# MJ808_clone_-_all_driver.net
KiCad netlist of a schematic drawn in EAGLE
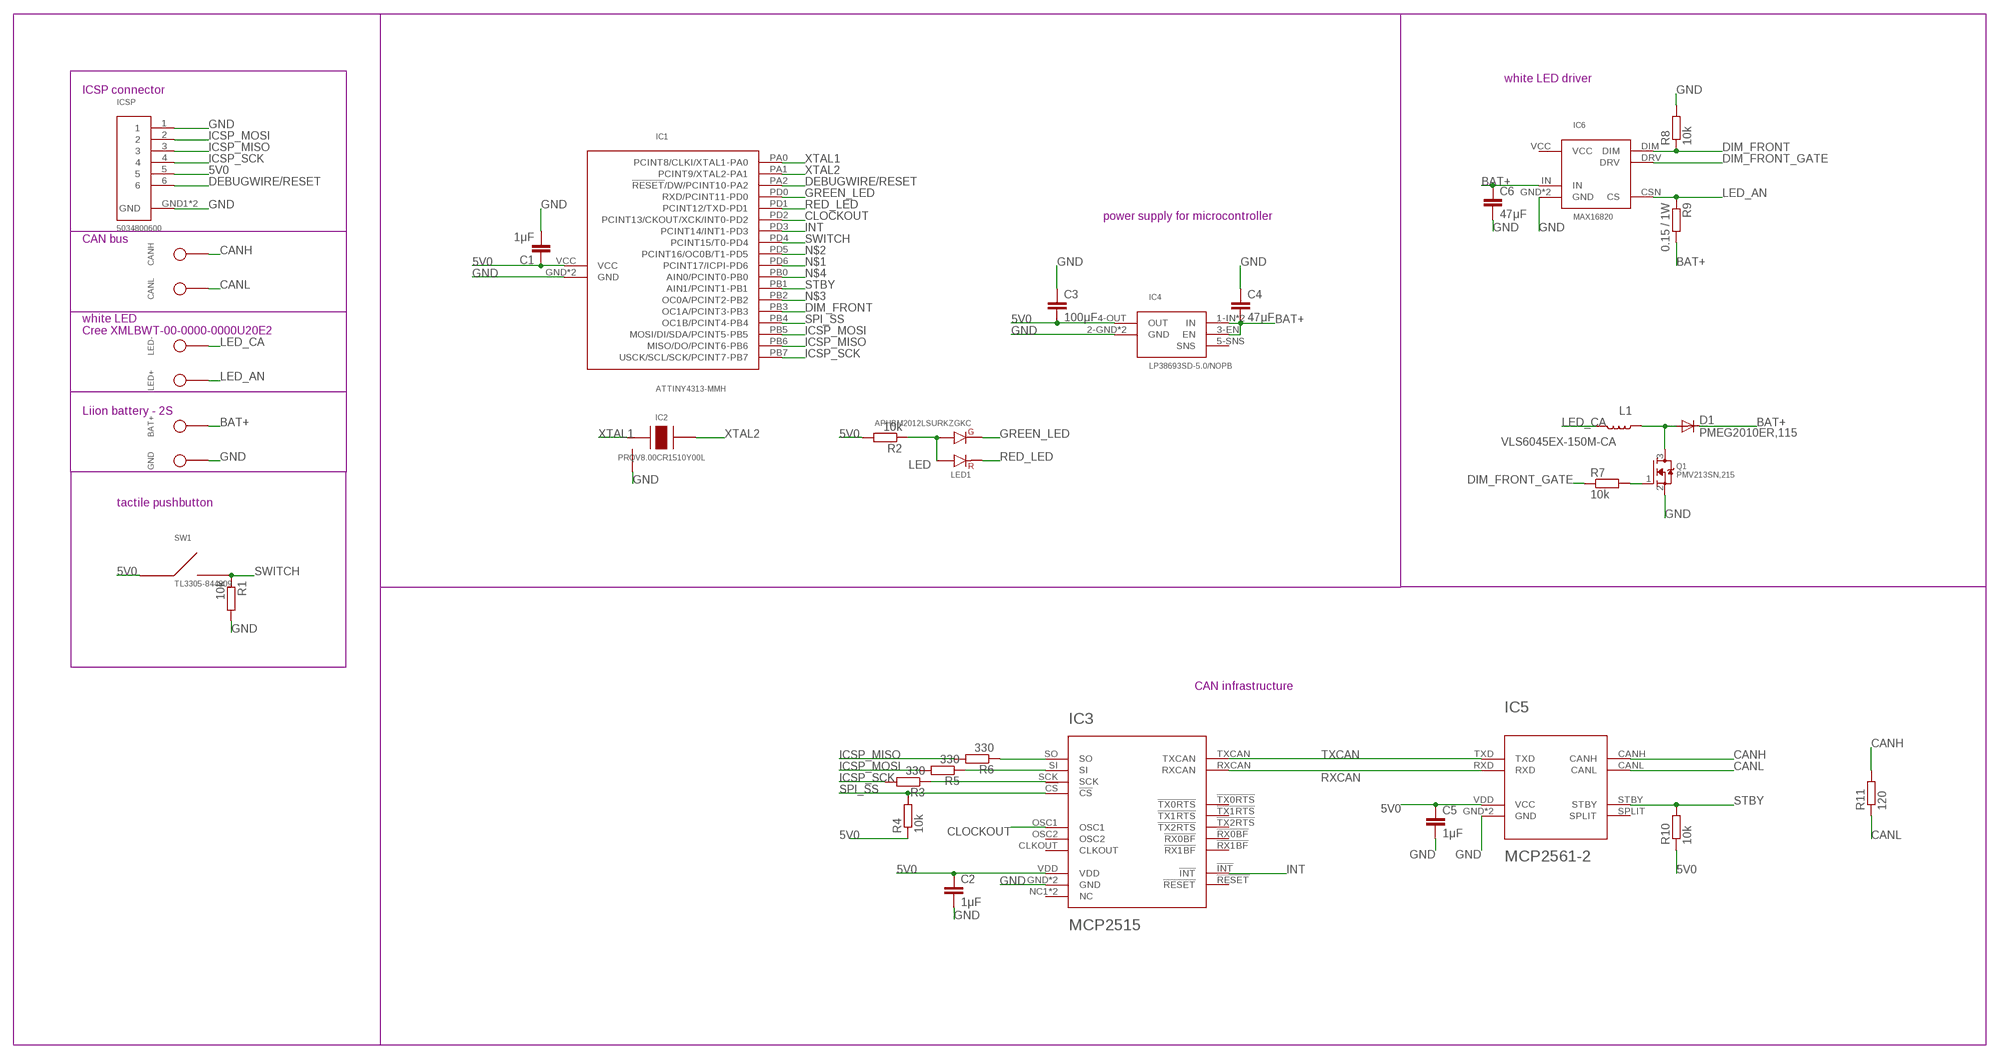
[diagram p0: schematic, sheet 1]

(export (version "E")
  (design (tool "Eeschema 10.0.6"))
  (components
    (comp (ref "BAT+")
      (value "LiIon + Terminal")
      (footprint "eagle-import:TH")
      (libsource (lib "eagle-import") (part "TP"))
    )
    (comp (ref "C1")
      (value "1μF")
      (footprint "eagle-import:C0402")
      (libsource (lib "eagle-import") (part "C-EUC0402"))
    )
    (comp (ref "C2")
      (value "1μF")
      (footprint "eagle-import:C0402")
      (libsource (lib "eagle-import") (part "C-EUC0402"))
    )
    (comp (ref "C3")
      (value "100μF")
      (footprint "eagle-import:C1206")
      (libsource (lib "eagle-import") (part "C-EUC1206"))
    )
    (comp (ref "C4")
      (value "47μF")
      (footprint "eagle-import:C0805")
      (libsource (lib "eagle-import") (part "C-EUC0805"))
    )
    (comp (ref "C5")
      (value "1μF")
      (footprint "eagle-import:C0402")
      (libsource (lib "eagle-import") (part "C-EUC0402"))
    )
    (comp (ref "C6")
      (value "47μF")
      (footprint "eagle-import:C0805")
      (libsource (lib "eagle-import") (part "C-EUC0805"))
    )
    (comp (ref "CANH")
      (value "CAN high")
      (footprint "eagle-import:TH")
      (libsource (lib "eagle-import") (part "TP"))
    )
    (comp (ref "CANL")
      (value "CAN low")
      (footprint "eagle-import:TH")
      (libsource (lib "eagle-import") (part "TP"))
    )
    (comp (ref "D1")
      (value "PMEG2010ER,115")
      (footprint "eagle-import:SOD123")
      (libsource (lib "eagle-import") (part "DIODE-SOD123"))
    )
    (comp (ref "GND")
      (value "LiIon - Terminal")
      (footprint "eagle-import:TH")
      (libsource (lib "eagle-import") (part "TP"))
    )
    (comp (ref "IC1")
      (value "ATTINY4313-MMH")
      (footprint "eagle-import:VQFN-20")
      (fields (field (name "SPICEPREFIX") "X"))
      (libsource (lib "eagle-import") (part "ATTINY4313VQFN-20"))
    )
    (comp (ref "IC2")
      (value "PRQV8.00CR1510Y00L")
      (footprint "eagle-import:SMT")
      (libsource (lib "eagle-import") (part "PRQV"))
    )
    (comp (ref "IC3")
      (value "MCP2515")
      (footprint "eagle-import:QFN20")
      (libsource (lib "eagle-import") (part "MCP2515-I-ML"))
    )
    (comp (ref "IC4")
      (value "LP38693SD-5.0/NOPB")
      (footprint "eagle-import:WSON6")
      (libsource (lib "eagle-import") (part "LP38693"))
    )
    (comp (ref "IC5")
      (value "MCP2561-2")
      (footprint "eagle-import:DFN10")
      (libsource (lib "eagle-import") (part "MCP2561-2"))
    )
    (comp (ref "IC6")
      (value "MAX16820")
      (footprint "eagle-import:TDFN-6-EP")
      (libsource (lib "eagle-import") (part "MAX16820"))
    )
    (comp (ref "ICSP")
      (value "5034800600")
      (footprint "eagle-import:SMT")
      (libsource (lib "eagle-import") (part "5034800600"))
    )
    (comp (ref "L1")
      (value "VLS6045EX-150M-CA")
      (footprint "eagle-import:SRN6045")
      (libsource (lib "eagle-import") (part "INDUCTOR-SRN6045-33UH"))
    )
    (comp (ref "LED+")
      (value "LED anode")
      (footprint "eagle-import:TH")
      (libsource (lib "eagle-import") (part "TP"))
    )
    (comp (ref "LED-")
      (value "LED cathode")
      (footprint "eagle-import:TH")
      (libsource (lib "eagle-import") (part "TP"))
    )
    (comp (ref "LED1")
      (value "APHBM2012LSURKZGKC")
      (footprint "eagle-import:SMD")
      (libsource (lib "eagle-import") (part "APHBM2012LSURKZGKC"))
    )
    (comp (ref "Q1")
      (value "PMV213SN,215")
      (footprint "eagle-import:SOT23")
      (libsource (lib "eagle-import") (part "MOSFET-NREFLOW"))
    )
    (comp (ref "R1")
      (value "10k")
      (footprint "eagle-import:R0402")
      (libsource (lib "eagle-import") (part "R-EU_R0402"))
    )
    (comp (ref "R2")
      (value "10k")
      (footprint "eagle-import:R0402")
      (libsource (lib "eagle-import") (part "R-EU_R0402"))
    )
    (comp (ref "R3")
      (value "330")
      (footprint "eagle-import:R0402")
      (libsource (lib "eagle-import") (part "R-EU_R0402"))
    )
    (comp (ref "R4")
      (value "10k")
      (footprint "eagle-import:R0402")
      (libsource (lib "eagle-import") (part "R-EU_R0402"))
    )
    (comp (ref "R5")
      (value "330")
      (footprint "eagle-import:R0402")
      (libsource (lib "eagle-import") (part "R-EU_R0402"))
    )
    (comp (ref "R6")
      (value "330")
      (footprint "eagle-import:R0402")
      (libsource (lib "eagle-import") (part "R-EU_R0402"))
    )
    (comp (ref "R7")
      (value "10k")
      (footprint "eagle-import:R0402")
      (libsource (lib "eagle-import") (part "R-EU_R0402"))
    )
    (comp (ref "R8")
      (value "10k")
      (footprint "eagle-import:R0402")
      (libsource (lib "eagle-import") (part "R-EU_R0402"))
    )
    (comp (ref "R9")
      (value "0.15 / 1W")
      (footprint "eagle-import:R1210")
      (libsource (lib "eagle-import") (part "R-EU_R1210"))
    )
    (comp (ref "R10")
      (value "10k")
      (footprint "eagle-import:R0402")
      (libsource (lib "eagle-import") (part "R-EU_R0402"))
    )
    (comp (ref "R11")
      (value "120")
      (footprint "eagle-import:R0805")
      (libsource (lib "eagle-import") (part "R-EU_R0805"))
    )
    (comp (ref "SW1")
      (value "TL3305-844809")
      (footprint "eagle-import:SMD")
      (libsource (lib "eagle-import") (part "TL3305-844809"))
    )
  )
  (nets
    (net (code "1") (name "/5V0") (class "Default")
      (node (ref "C1") (pin "1") (pinfunction "1_1") (pintype "passive"))
      (node (ref "C2") (pin "1") (pinfunction "1_1") (pintype "passive"))
      (node (ref "C3") (pin "2") (pinfunction "2_2") (pintype "passive"))
      (node (ref "C5") (pin "1") (pinfunction "1_1") (pintype "passive"))
      (node (ref "IC1") (pin "VCC") (pinfunction "VCC_VCC") (pintype "bidirectional"))
      (node (ref "IC3") (pin "VDD") (pinfunction "VDD_VDD") (pintype "power_in"))
      (node (ref "IC4") (pin "4-OUT") (pinfunction "OUT_4-OUT") (pintype "bidirectional"))
      (node (ref "IC5") (pin "VDD") (pinfunction "VCC_VDD") (pintype "power_in"))
      (node (ref "ICSP") (pin "5") (pinfunction "5_5") (pintype "bidirectional"))
      (node (ref "R10") (pin "1") (pinfunction "1_1") (pintype "passive"))
      (node (ref "R2") (pin "2") (pinfunction "2_2") (pintype "passive"))
      (node (ref "R4") (pin "1") (pinfunction "1_1") (pintype "passive"))
      (node (ref "SW1") (pin "1") (pinfunction "P$1_1") (pintype "bidirectional"))
      (node (ref "SW1") (pin "2") (pinfunction "P$1_2") (pintype "bidirectional"))
    )
    (net (code "2") (name "/BAT+") (class "Default")
      (node (ref "BAT+") (pin "TP$1") (pinfunction "TP$1_TP$1") (pintype "bidirectional"))
      (node (ref "C4") (pin "2") (pinfunction "2_2") (pintype "passive"))
      (node (ref "C6") (pin "1") (pinfunction "1_1") (pintype "passive"))
      (node (ref "D1") (pin "C") (pinfunction "C_C") (pintype "passive"))
      (node (ref "IC4") (pin "1-IN") (pinfunction "IN_1-IN") (pintype "bidirectional"))
      (node (ref "IC4") (pin "3-EN") (pinfunction "EN_3-EN") (pintype "bidirectional"))
      (node (ref "IC4") (pin "6-IN") (pinfunction "IN_6-IN") (pintype "bidirectional"))
      (node (ref "IC6") (pin "IN") (pinfunction "IN_IN") (pintype "power_in"))
      (node (ref "R9") (pin "2") (pinfunction "2_2") (pintype "passive"))
    )
    (net (code "3") (name "/CANH") (class "Default")
      (node (ref "CANH") (pin "TP$1") (pinfunction "TP$1_TP$1") (pintype "bidirectional"))
      (node (ref "IC5") (pin "CANH") (pinfunction "CANH_CANH") (pintype "bidirectional"))
      (node (ref "R11") (pin "2") (pinfunction "2_2") (pintype "passive"))
    )
    (net (code "4") (name "/CANL") (class "Default")
      (node (ref "CANL") (pin "TP$1") (pinfunction "TP$1_TP$1") (pintype "bidirectional"))
      (node (ref "IC5") (pin "CANL") (pinfunction "CANL_CANL") (pintype "bidirectional"))
      (node (ref "R11") (pin "1") (pinfunction "1_1") (pintype "passive"))
    )
    (net (code "5") (name "/CLOCKOUT") (class "Default")
      (node (ref "IC1") (pin "PD2") (pinfunction "PCINT13/CKOUT/XCK/INT0-PD2_PD2") (pintype "bidirectional"))
      (node (ref "IC3") (pin "OSC1") (pinfunction "OSC1_OSC1") (pintype "bidirectional"))
    )
    (net (code "6") (name "/DEBUGWIRE{slash}RESET") (class "Default")
      (node (ref "IC1") (pin "PA2") (pinfunction "~{RESET}/DW/PCINT10-PA2_PA2") (pintype "bidirectional"))
      (node (ref "ICSP") (pin "6") (pinfunction "6_6") (pintype "bidirectional"))
    )
    (net (code "7") (name "/DIM_FRONT") (class "Default")
      (node (ref "IC1") (pin "PB3") (pinfunction "OC1A/PCINT3-PB3_PB3") (pintype "bidirectional"))
      (node (ref "IC6") (pin "DIM") (pinfunction "DIM_DIM") (pintype "bidirectional"))
      (node (ref "R8") (pin "1") (pinfunction "1_1") (pintype "passive"))
    )
    (net (code "8") (name "/DIM_FRONT_GATE") (class "Default")
      (node (ref "IC6") (pin "DRV") (pinfunction "DRV_DRV") (pintype "bidirectional"))
      (node (ref "R7") (pin "1") (pinfunction "1_1") (pintype "passive"))
    )
    (net (code "9") (name "/GND") (class "Default")
      (node (ref "C1") (pin "2") (pinfunction "2_2") (pintype "passive"))
      (node (ref "C2") (pin "2") (pinfunction "2_2") (pintype "passive"))
      (node (ref "C3") (pin "1") (pinfunction "1_1") (pintype "passive"))
      (node (ref "C4") (pin "1") (pinfunction "1_1") (pintype "passive"))
      (node (ref "C5") (pin "2") (pinfunction "2_2") (pintype "passive"))
      (node (ref "C6") (pin "2") (pinfunction "2_2") (pintype "passive"))
      (node (ref "GND") (pin "TP$1") (pinfunction "TP$1_TP$1") (pintype "bidirectional"))
      (node (ref "IC1") (pin "GND") (pinfunction "GND_GND") (pintype "bidirectional"))
      (node (ref "IC1") (pin "GND1") (pinfunction "GND_GND1") (pintype "bidirectional"))
      (node (ref "IC2") (pin "GND") (pinfunction "GND_GND") (pintype "bidirectional"))
      (node (ref "IC3") (pin "GND") (pinfunction "GND_GND") (pintype "power_in"))
      (node (ref "IC3") (pin "GND6") (pinfunction "GND_GND6") (pintype "power_in"))
      (node (ref "IC4") (pin "2-GND") (pinfunction "GND_2-GND") (pintype "bidirectional"))
      (node (ref "IC4") (pin "GND1") (pinfunction "GND_GND1") (pintype "bidirectional"))
      (node (ref "IC5") (pin "GND") (pinfunction "GND_GND") (pintype "power_in"))
      (node (ref "IC5") (pin "VSS") (pinfunction "GND_VSS") (pintype "power_in"))
      (node (ref "IC6") (pin "GND") (pinfunction "GND_GND") (pintype "power_in"))
      (node (ref "IC6") (pin "GND1") (pinfunction "GND_GND1") (pintype "power_in"))
      (node (ref "ICSP") (pin "1") (pinfunction "1_1") (pintype "bidirectional"))
      (node (ref "ICSP") (pin "GND1") (pinfunction "GND_GND1") (pintype "bidirectional"))
      (node (ref "ICSP") (pin "GND2") (pinfunction "GND_GND2") (pintype "bidirectional"))
      (node (ref "Q1") (pin "2") (pinfunction "S_2") (pintype "bidirectional"))
      (node (ref "R1") (pin "2") (pinfunction "2_2") (pintype "passive"))
      (node (ref "R8") (pin "2") (pinfunction "2_2") (pintype "passive"))
    )
    (net (code "10") (name "/GREEN_LED") (class "Default")
      (node (ref "IC1") (pin "PD0") (pinfunction "RXD/PCINT11-PD0_PD0") (pintype "bidirectional"))
      (node (ref "LED1") (pin "3") (pinfunction "3_3") (pintype "bidirectional"))
    )
    (net (code "11") (name "/ICSP_MISO") (class "Default")
      (node (ref "IC1") (pin "PB6") (pinfunction "MISO/DO/PCINT6-PB6_PB6") (pintype "bidirectional"))
      (node (ref "ICSP") (pin "3") (pinfunction "3_3") (pintype "bidirectional"))
      (node (ref "R6") (pin "2") (pinfunction "2_2") (pintype "passive"))
    )
    (net (code "12") (name "/ICSP_MOSI") (class "Default")
      (node (ref "IC1") (pin "PB5") (pinfunction "MOSI/DI/SDA/PCINT5-PB5_PB5") (pintype "bidirectional"))
      (node (ref "ICSP") (pin "2") (pinfunction "2_2") (pintype "bidirectional"))
      (node (ref "R5") (pin "2") (pinfunction "2_2") (pintype "passive"))
    )
    (net (code "13") (name "/ICSP_SCK") (class "Default")
      (node (ref "IC1") (pin "PB7") (pinfunction "USCK/SCL/SCK/PCINT7-PB7_PB7") (pintype "bidirectional"))
      (node (ref "ICSP") (pin "4") (pinfunction "4_4") (pintype "bidirectional"))
      (node (ref "R3") (pin "2") (pinfunction "2_2") (pintype "passive"))
    )
    (net (code "14") (name "/INT") (class "Default")
      (node (ref "IC1") (pin "PD3") (pinfunction "PCINT14/INT1-PD3_PD3") (pintype "bidirectional"))
      (node (ref "IC3") (pin "!INT!") (pinfunction "~{INT}_!INT!") (pintype "bidirectional"))
    )
    (net (code "15") (name "/LED") (class "Default")
      (node (ref "LED1") (pin "1") (pinfunction "1_1") (pintype "bidirectional"))
      (node (ref "LED1") (pin "4") (pinfunction "4_4") (pintype "bidirectional"))
      (node (ref "R2") (pin "1") (pinfunction "1_1") (pintype "passive"))
    )
    (net (code "16") (name "/LED_AN") (class "Default")
      (node (ref "IC6") (pin "CSN") (pinfunction "CS_CSN") (pintype "bidirectional"))
      (node (ref "LED+") (pin "TP$1") (pinfunction "TP$1_TP$1") (pintype "bidirectional"))
      (node (ref "R9") (pin "1") (pinfunction "1_1") (pintype "passive"))
    )
    (net (code "17") (name "/LED_CA") (class "Default")
      (node (ref "L1") (pin "2") (pinfunction "2_2") (pintype "passive"))
      (node (ref "LED-") (pin "TP$1") (pinfunction "TP$1_TP$1") (pintype "bidirectional"))
    )
    (net (code "18") (name "/N$1") (class "Default")
      (node (ref "IC1") (pin "PD6") (pinfunction "PCINT17/ICPI-PD6_PD6") (pintype "bidirectional"))
    )
    (net (code "19") (name "/N$2") (class "Default")
      (node (ref "IC1") (pin "PD5") (pinfunction "PCINT16/OC0B/T1-PD5_PD5") (pintype "bidirectional"))
    )
    (net (code "20") (name "/N$3") (class "Default")
      (node (ref "IC1") (pin "PB2") (pinfunction "OC0A/PCINT2-PB2_PB2") (pintype "bidirectional"))
    )
    (net (code "21") (name "/N$4") (class "Default")
      (node (ref "IC1") (pin "PB0") (pinfunction "AIN0/PCINT0-PB0_PB0") (pintype "bidirectional"))
    )
    (net (code "22") (name "/RED_LED") (class "Default")
      (node (ref "IC1") (pin "PD1") (pinfunction "PCINT12/TXD-PD1_PD1") (pintype "bidirectional"))
      (node (ref "LED1") (pin "2") (pinfunction "2_2") (pintype "bidirectional"))
    )
    (net (code "23") (name "/RXCAN") (class "Default")
      (node (ref "IC3") (pin "RXCAN") (pinfunction "RXCAN_RXCAN") (pintype "input"))
      (node (ref "IC5") (pin "RXD") (pinfunction "RXD_RXD") (pintype "output"))
    )
    (net (code "24") (name "/SPI_SS") (class "Default")
      (node (ref "IC1") (pin "PB4") (pinfunction "OC1B/PCINT4-PB4_PB4") (pintype "bidirectional"))
      (node (ref "IC3") (pin "!CS!") (pinfunction "~{CS}_!CS!") (pintype "bidirectional"))
      (node (ref "R4") (pin "2") (pinfunction "2_2") (pintype "passive"))
    )
    (net (code "25") (name "/STBY") (class "Default")
      (node (ref "IC1") (pin "PB1") (pinfunction "AIN1/PCINT1-PB1_PB1") (pintype "bidirectional"))
      (node (ref "IC5") (pin "STBY") (pinfunction "STBY_STBY") (pintype "bidirectional"))
      (node (ref "R10") (pin "2") (pinfunction "2_2") (pintype "passive"))
    )
    (net (code "26") (name "/SWITCH") (class "Default")
      (node (ref "IC1") (pin "PD4") (pinfunction "PCINT15/T0-PD4_PD4") (pintype "bidirectional"))
      (node (ref "R1") (pin "1") (pinfunction "1_1") (pintype "passive"))
      (node (ref "SW1") (pin "3") (pinfunction "P$2_3") (pintype "bidirectional"))
      (node (ref "SW1") (pin "4") (pinfunction "P$2_4") (pintype "bidirectional"))
    )
    (net (code "27") (name "/TXCAN") (class "Default")
      (node (ref "IC3") (pin "TXCAN") (pinfunction "TXCAN_TXCAN") (pintype "output"))
      (node (ref "IC5") (pin "TXD") (pinfunction "TXD_TXD") (pintype "input"))
    )
    (net (code "28") (name "/VCC") (class "Default")
      (node (ref "IC6") (pin "VCC") (pinfunction "VCC_VCC") (pintype "power_in"))
    )
    (net (code "29") (name "/XTAL1") (class "Default")
      (node (ref "IC1") (pin "PA0") (pinfunction "PCINT8/CLKI/XTAL1-PA0_PA0") (pintype "bidirectional"))
      (node (ref "IC2") (pin "XTAL1") (pinfunction "XTAL1_XTAL1") (pintype "bidirectional"))
    )
    (net (code "30") (name "/XTAL2") (class "Default")
      (node (ref "IC1") (pin "PA1") (pinfunction "PCINT9/XTAL2-PA1_PA1") (pintype "bidirectional"))
      (node (ref "IC2") (pin "XTAL2") (pinfunction "XTAL2_XTAL2") (pintype "bidirectional"))
    )
    (net (code "31") (name "Net-(IC3-PadSCK)") (class "Default")
      (node (ref "IC3") (pin "SCK") (pinfunction "SCK_SCK") (pintype "bidirectional"))
      (node (ref "R3") (pin "1") (pinfunction "1_1") (pintype "passive"))
    )
    (net (code "32") (name "Net-(IC3-PadSI)") (class "Default")
      (node (ref "IC3") (pin "SI") (pinfunction "SI_SI") (pintype "input"))
      (node (ref "R5") (pin "1") (pinfunction "1_1") (pintype "passive"))
    )
    (net (code "33") (name "Net-(IC3-PadSO)") (class "Default")
      (node (ref "IC3") (pin "SO") (pinfunction "SO_SO") (pintype "output"))
      (node (ref "R6") (pin "1") (pinfunction "1_1") (pintype "passive"))
    )
    (net (code "34") (name "Net-(Q1-D)") (class "Default")
      (node (ref "D1") (pin "A") (pinfunction "A_A") (pintype "passive"))
      (node (ref "L1") (pin "1") (pinfunction "1_1") (pintype "passive"))
      (node (ref "Q1") (pin "3") (pinfunction "D_3") (pintype "bidirectional"))
    )
    (net (code "35") (name "Net-(Q1-G)") (class "Default")
      (node (ref "Q1") (pin "1") (pinfunction "G_1") (pintype "bidirectional"))
      (node (ref "R7") (pin "2") (pinfunction "2_2") (pintype "passive"))
    )
    (net (code "36") (name "unconnected-(IC3-NC-PadNC1)") (class "Default")
      (node (ref "IC3") (pin "NC1") (pinfunction "NC_NC1") (pintype "no_connect"))
    )
    (net (code "37") (name "unconnected-(IC3-NC-PadNC2)") (class "Default")
      (node (ref "IC3") (pin "NC2") (pinfunction "NC_NC2") (pintype "no_connect"))
    )
    (net (code "38") (name "unconnected-(IC3-PadCLKOUT)") (class "Default")
      (node (ref "IC3") (pin "CLKOUT") (pinfunction "CLKOUT_CLKOUT") (pintype "bidirectional"))
    )
    (net (code "39") (name "unconnected-(IC3-PadOSC2)") (class "Default")
      (node (ref "IC3") (pin "OSC2") (pinfunction "OSC2_OSC2") (pintype "bidirectional"))
    )
    (net (code "40") (name "unconnected-(IC3-~{RESET}-Pad!RESET!)") (class "Default")
      (node (ref "IC3") (pin "!RESET!") (pinfunction "~{RESET}_!RESET!") (pintype "bidirectional"))
    )
    (net (code "41") (name "unconnected-(IC3-~{RX0BF}-Pad!RX0BF!)") (class "Default")
      (node (ref "IC3") (pin "!RX0BF!") (pinfunction "~{RX0BF}_!RX0BF!") (pintype "bidirectional"))
    )
    (net (code "42") (name "unconnected-(IC3-~{RX1BF}-Pad!RX1BF!)") (class "Default")
      (node (ref "IC3") (pin "!RX1BF!") (pinfunction "~{RX1BF}_!RX1BF!") (pintype "bidirectional"))
    )
    (net (code "43") (name "unconnected-(IC3-~{TX0RTS}-Pad!TX0RTS!)") (class "Default")
      (node (ref "IC3") (pin "!TX0RTS!") (pinfunction "~{TX0RTS}_!TX0RTS!") (pintype "bidirectional"))
    )
    (net (code "44") (name "unconnected-(IC3-~{TX1RTS}-Pad!TX1RTS!)") (class "Default")
      (node (ref "IC3") (pin "!TX1RTS!") (pinfunction "~{TX1RTS}_!TX1RTS!") (pintype "bidirectional"))
    )
    (net (code "45") (name "unconnected-(IC3-~{TX2RTS}-Pad!TX2RTS!)") (class "Default")
      (node (ref "IC3") (pin "!TX2RTS!") (pinfunction "~{TX2RTS}_!TX2RTS!") (pintype "bidirectional"))
    )
    (net (code "46") (name "unconnected-(IC4-SNS-Pad5-SNS)") (class "Default")
      (node (ref "IC4") (pin "5-SNS") (pinfunction "SNS_5-SNS") (pintype "bidirectional"))
    )
    (net (code "47") (name "unconnected-(IC5-PadSPLIT)") (class "Default")
      (node (ref "IC5") (pin "SPLIT") (pinfunction "SPLIT_SPLIT") (pintype "bidirectional"))
    )
  )
)
